# SectionC_BreakOut.net
KiCad netlist of a schematic drawn in Altium Designer
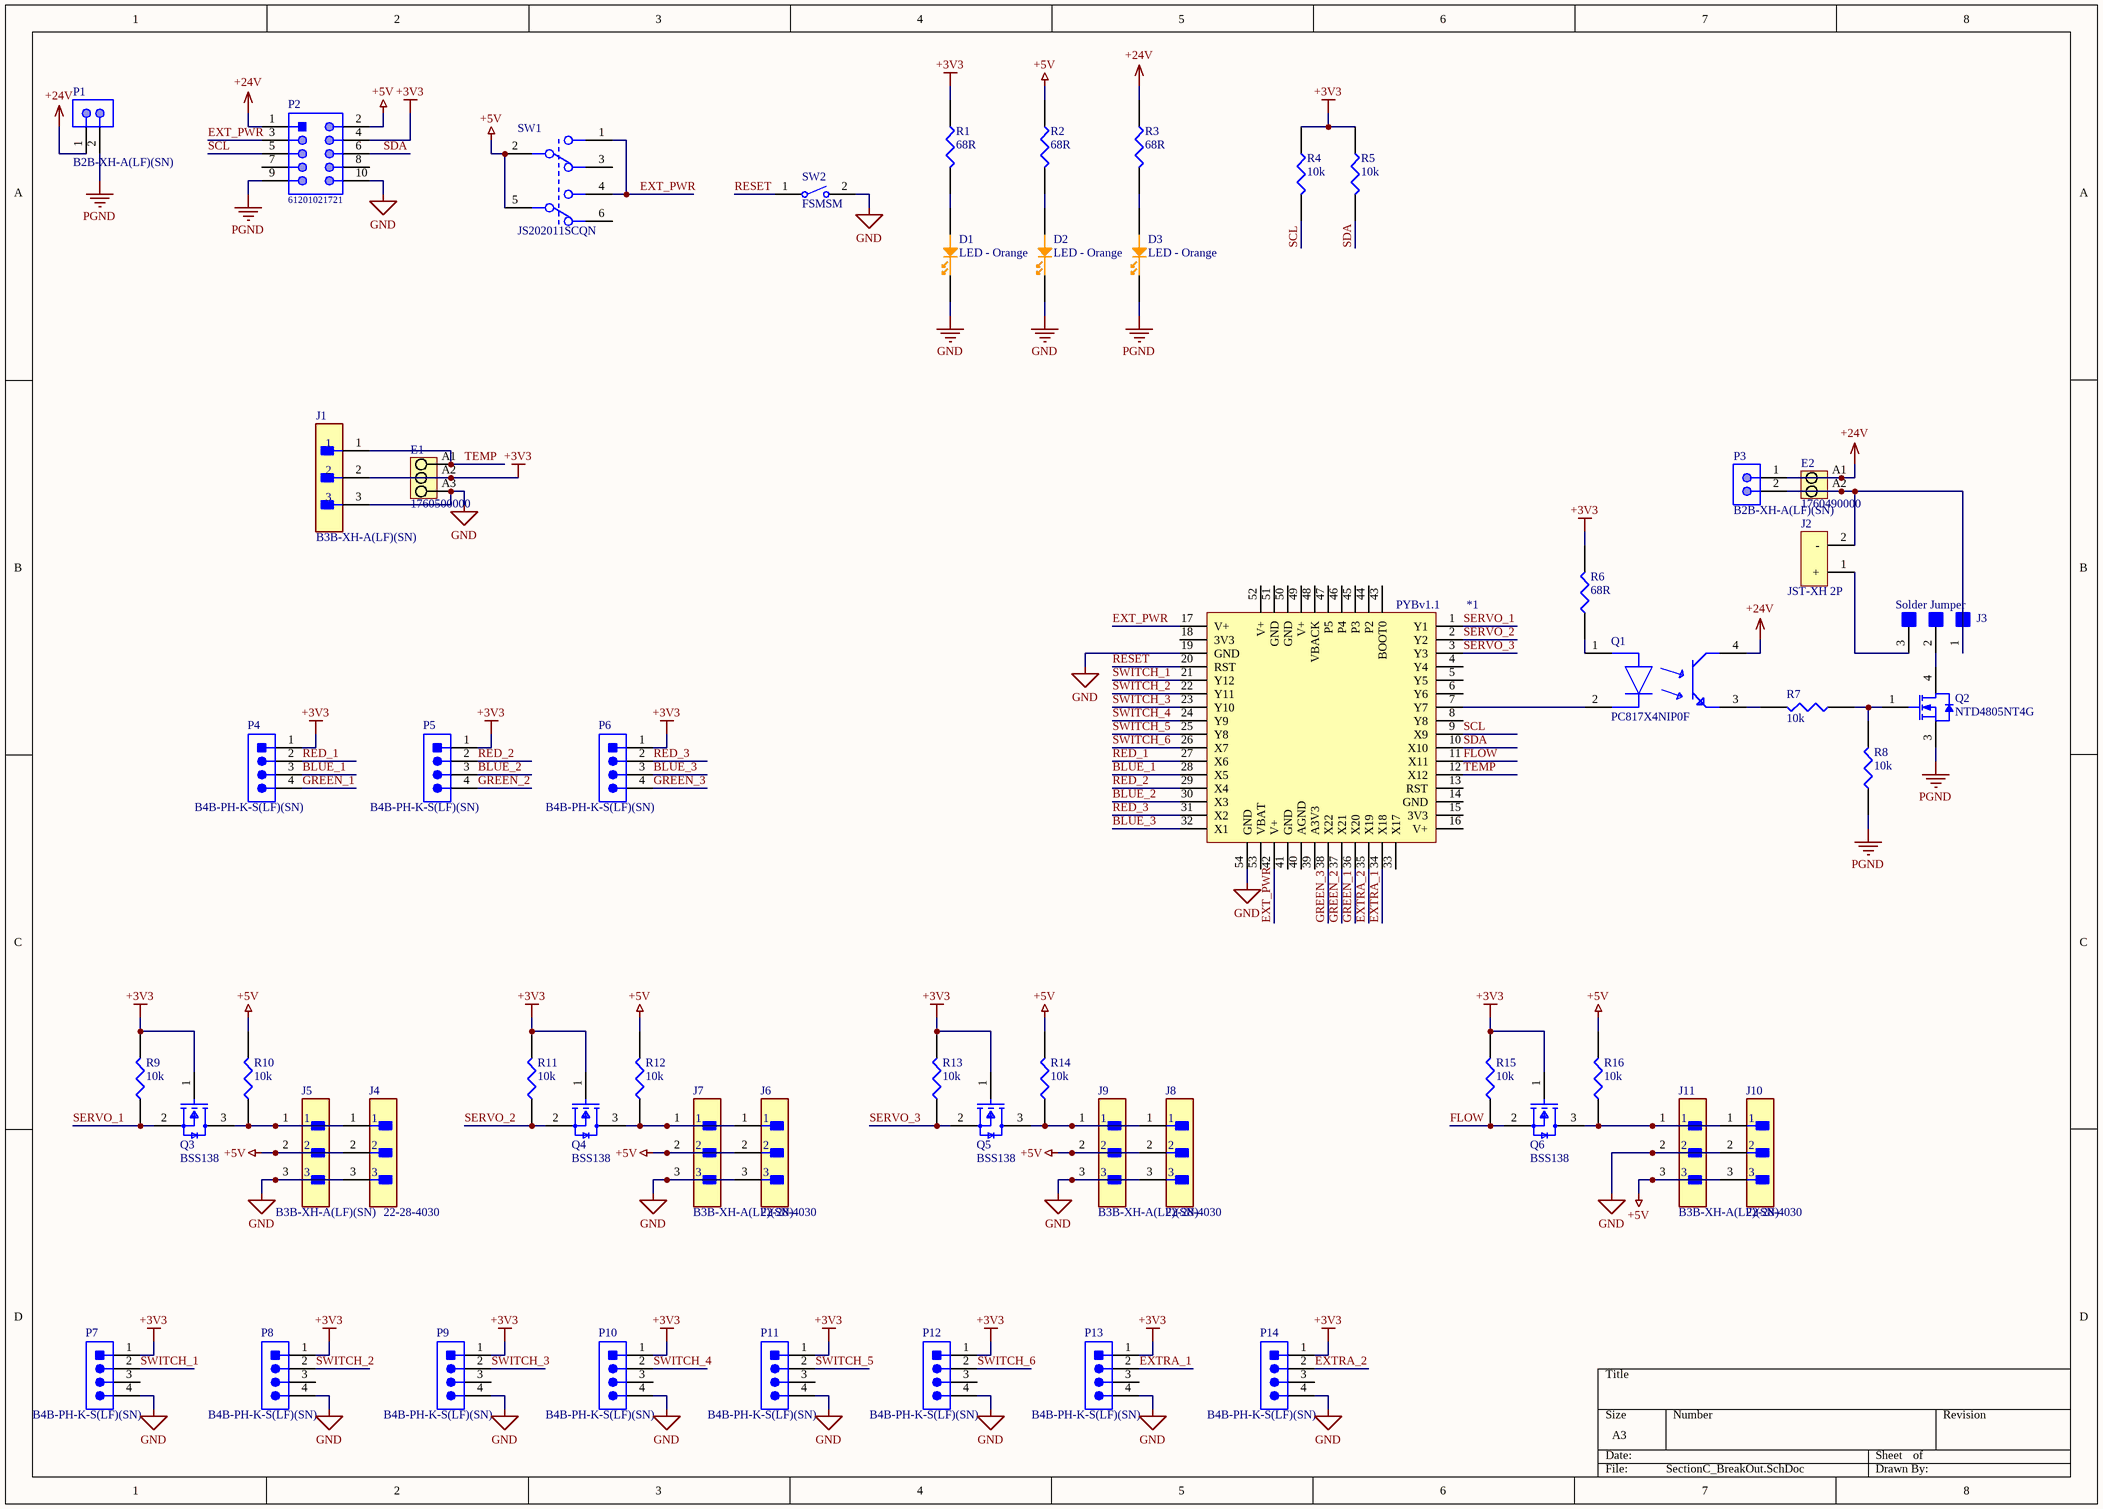
[diagram p0: SectionC_BreakOut.SchDoc]

(export (version "E")
  (design (tool "Eeschema 10.0.6"))
  (components
    (comp (ref "*1")
      (value "PYBv1.1")
      (footprint "PYBv1.1")
      (libsource (lib "SectionC_BreakOut") (part "PYBv1.1"))
    )
    (comp (ref "D1")
      (value "LED - Orange")
      (footprint "LED0603-Orange")
      (description "LED ORANGE CLEAR SMD")
      (fields
        (field (name "MANUFACTURER") "Vishay Lite-On")
        (field (name "MANUFACTURER PART NUMBER") "LTST-C191KFKT")
      )
      (libsource (lib "Limit_Switch_RGB") (part "LTST-C191KFKT"))
    )
    (comp (ref "D2")
      (value "LED - Orange")
      (footprint "LED0603-Orange")
      (description "LED ORANGE CLEAR SMD")
      (fields
        (field (name "MANUFACTURER") "Vishay Lite-On")
        (field (name "MANUFACTURER PART NUMBER") "LTST-C191KFKT")
      )
      (libsource (lib "Limit_Switch_RGB") (part "LTST-C191KFKT"))
    )
    (comp (ref "D3")
      (value "LED - Orange")
      (footprint "LED0603-Orange")
      (description "LED ORANGE CLEAR SMD")
      (fields
        (field (name "MANUFACTURER") "Vishay Lite-On")
        (field (name "MANUFACTURER PART NUMBER") "LTST-C191KFKT")
      )
      (libsource (lib "Limit_Switch_RGB") (part "LTST-C191KFKT"))
    )
    (comp (ref "E1")
      (value "1760500000")
      (footprint "PM_5_08_90_03")
      (description "OMNIMATE Signal - series PM")
      (fields (field (name "MANUFACTURER") "Weidmueller"))
      (libsource (lib "Altium Content Vault") (part "Terminal_03_1x03"))
    )
    (comp (ref "E2")
      (value "1760490000")
      (footprint "PM_5_08_90_02")
      (description "OMNIMATE Signal - series PM")
      (fields (field (name "MANUFACTURER") "Weidmueller"))
      (libsource (lib "Altium Content Vault") (part "Terminal_02_1x02"))
    )
    (comp (ref "J1")
      (value "B3B-XH-A(LF)(SN)")
      (footprint "FP-B3B-XH-A_LF_SN-MFG")
      (description "CONN HEADER VERT 3POS 2.5MM")
      (fields
        (field (name "OCTOPART") "https://octopart.com/b3b-xh-a%28lf%29%28sn%29-jst-3990185")
        (field (name "MANUFACTURER") "JST")
      )
      (libsource (lib "") (part "0d3f023dd272f625e17a2be33dea85f_1"))
    )
    (comp (ref "J2")
      (value "JST-XH 2P")
      (footprint "JST-XH 2P")
      (description "JST-XH 2 POS 2.5mm Solder ST Thru-Hole Box")
      (fields
        (field (name "MANUFACTURER") "JST")
        (field (name "MANUFACTURER PART NUMBER") "B2B-XH-A(LF)(SN)")
      )
      (libsource (lib "SectionE_BreakOut") (part "B2B-XH-A(LF)(SN)"))
    )
    (comp (ref "J3")
      (value "Solder Jumper")
      (footprint "Solder Jumper")
      (libsource (lib "SectionE_BreakOut") (part "Solder Jumper"))
    )
    (comp (ref "J4")
      (value "22-28-4030")
      (footprint "FP-22-28-4030-MFG")
      (description "CONN HEADER VERT 3POS 2.54MM")
      (fields
        (field (name "OCTOPART") "https://octopart.com/0022284030-molex-10476094")
        (field (name "MANUFACTURER") "Molex")
      )
      (libsource (lib "Altium Content Vault") (part "0d3f023dd272f625e17a2be33dea85f"))
    )
    (comp (ref "J5")
      (value "B3B-XH-A(LF)(SN)")
      (footprint "FP-B3B-XH-A_LF_SN-MFG")
      (description "CONN HEADER VERT 3POS 2.5MM")
      (fields
        (field (name "OCTOPART") "https://octopart.com/b3b-xh-a%28lf%29%28sn%29-jst-3990185")
        (field (name "MANUFACTURER") "JST")
      )
      (libsource (lib "Altium Content Vault") (part "0d3f023dd272f625e17a2be33dea85f"))
    )
    (comp (ref "J6")
      (value "22-28-4030")
      (footprint "FP-22-28-4030-MFG")
      (description "CONN HEADER VERT 3POS 2.54MM")
      (fields
        (field (name "OCTOPART") "https://octopart.com/0022284030-molex-10476094")
        (field (name "MANUFACTURER") "Molex")
      )
      (libsource (lib "Altium Content Vault") (part "0d3f023dd272f625e17a2be33dea85f"))
    )
    (comp (ref "J7")
      (value "B3B-XH-A(LF)(SN)")
      (footprint "FP-B3B-XH-A_LF_SN-MFG")
      (description "CONN HEADER VERT 3POS 2.5MM")
      (fields
        (field (name "OCTOPART") "https://octopart.com/b3b-xh-a%28lf%29%28sn%29-jst-3990185")
        (field (name "MANUFACTURER") "JST")
      )
      (libsource (lib "Altium Content Vault") (part "0d3f023dd272f625e17a2be33dea85f"))
    )
    (comp (ref "J8")
      (value "22-28-4030")
      (footprint "FP-22-28-4030-MFG")
      (description "CONN HEADER VERT 3POS 2.54MM")
      (fields
        (field (name "OCTOPART") "https://octopart.com/0022284030-molex-10476094")
        (field (name "MANUFACTURER") "Molex")
      )
      (libsource (lib "Altium Content Vault") (part "0d3f023dd272f625e17a2be33dea85f"))
    )
    (comp (ref "J9")
      (value "B3B-XH-A(LF)(SN)")
      (footprint "FP-B3B-XH-A_LF_SN-MFG")
      (description "CONN HEADER VERT 3POS 2.5MM")
      (fields
        (field (name "OCTOPART") "https://octopart.com/b3b-xh-a%28lf%29%28sn%29-jst-3990185")
        (field (name "MANUFACTURER") "JST")
      )
      (libsource (lib "Altium Content Vault") (part "0d3f023dd272f625e17a2be33dea85f"))
    )
    (comp (ref "J10")
      (value "22-28-4030")
      (footprint "FP-22-28-4030-MFG")
      (description "CONN HEADER VERT 3POS 2.54MM")
      (fields
        (field (name "OCTOPART") "https://octopart.com/0022284030-molex-10476094")
        (field (name "MANUFACTURER") "Molex")
      )
      (libsource (lib "Altium Content Vault") (part "0d3f023dd272f625e17a2be33dea85f"))
    )
    (comp (ref "J11")
      (value "B3B-XH-A(LF)(SN)")
      (footprint "FP-B3B-XH-A_LF_SN-MFG")
      (description "CONN HEADER VERT 3POS 2.5MM")
      (fields
        (field (name "OCTOPART") "https://octopart.com/b3b-xh-a%28lf%29%28sn%29-jst-3990185")
        (field (name "MANUFACTURER") "JST")
      )
      (libsource (lib "Altium Content Vault") (part "0d3f023dd272f625e17a2be33dea85f"))
    )
    (comp (ref "P1")
      (value "B2B-XH-A(LF)(SN)")
      (footprint "JST-B2B-XH-A_V")
      (fields (field (name "MANUFACTURER") "JST"))
      (libsource (lib "") (part "CN-1P-M-R2_1"))
    )
    (comp (ref "P2")
      (value "61201021721")
      (footprint "61201021721")
      (description "Male Box Header WR-BHD, THT, Angled, pitch 2.54 mm, 10 pins")
      (fields (field (name "MANUFACTURER") "Wurth Elektronik") (field (name "PUBLISHER") "WurthElektronik"))
      (libsource (lib "Altium Content Vault") (part "WE-CN-2P-M-R10"))
    )
    (comp (ref "P3")
      (value "B2B-XH-A(LF)(SN)")
      (footprint "JST-B2B-XH-A_V")
      (fields (field (name "MANUFACTURER") "JST"))
      (libsource (lib "Altium Content Vault") (part "CN-1P-M-R2"))
    )
    (comp (ref "P4")
      (value "B4B-PH-K-S(LF)(SN)")
      (footprint "JST-B4B-PH-K-S_V")
      (fields (field (name "MANUFACTURER") "JST"))
      (libsource (lib "Altium Content Vault") (part "CN-1P-M-R4"))
    )
    (comp (ref "P5")
      (value "B4B-PH-K-S(LF)(SN)")
      (footprint "JST-B4B-PH-K-S_V")
      (fields (field (name "MANUFACTURER") "JST"))
      (libsource (lib "Altium Content Vault") (part "CN-1P-M-R4"))
    )
    (comp (ref "P6")
      (value "B4B-PH-K-S(LF)(SN)")
      (footprint "JST-B4B-PH-K-S_V")
      (fields (field (name "MANUFACTURER") "JST"))
      (libsource (lib "Altium Content Vault") (part "CN-1P-M-R4"))
    )
    (comp (ref "P7")
      (value "B4B-PH-K-S(LF)(SN)")
      (footprint "JST-B4B-PH-K-S_V")
      (fields (field (name "MANUFACTURER") "JST"))
      (libsource (lib "Altium Content Vault") (part "CN-1P-M-R4"))
    )
    (comp (ref "P8")
      (value "B4B-PH-K-S(LF)(SN)")
      (footprint "JST-B4B-PH-K-S_V")
      (fields (field (name "MANUFACTURER") "JST"))
      (libsource (lib "Altium Content Vault") (part "CN-1P-M-R4"))
    )
    (comp (ref "P9")
      (value "B4B-PH-K-S(LF)(SN)")
      (footprint "JST-B4B-PH-K-S_V")
      (fields (field (name "MANUFACTURER") "JST"))
      (libsource (lib "Altium Content Vault") (part "CN-1P-M-R4"))
    )
    (comp (ref "P10")
      (value "B4B-PH-K-S(LF)(SN)")
      (footprint "JST-B4B-PH-K-S_V")
      (fields (field (name "MANUFACTURER") "JST"))
      (libsource (lib "Altium Content Vault") (part "CN-1P-M-R4"))
    )
    (comp (ref "P11")
      (value "B4B-PH-K-S(LF)(SN)")
      (footprint "JST-B4B-PH-K-S_V")
      (fields (field (name "MANUFACTURER") "JST"))
      (libsource (lib "Altium Content Vault") (part "CN-1P-M-R4"))
    )
    (comp (ref "P12")
      (value "B4B-PH-K-S(LF)(SN)")
      (footprint "JST-B4B-PH-K-S_V")
      (fields (field (name "MANUFACTURER") "JST"))
      (libsource (lib "Altium Content Vault") (part "CN-1P-M-R4"))
    )
    (comp (ref "P13")
      (value "B4B-PH-K-S(LF)(SN)")
      (footprint "JST-B4B-PH-K-S_V")
      (fields (field (name "MANUFACTURER") "JST"))
      (libsource (lib "Altium Content Vault") (part "CN-1P-M-R4"))
    )
    (comp (ref "P14")
      (value "B4B-PH-K-S(LF)(SN)")
      (footprint "JST-B4B-PH-K-S_V")
      (fields (field (name "MANUFACTURER") "JST"))
      (libsource (lib "Altium Content Vault") (part "CN-1P-M-R4"))
    )
    (comp (ref "Q1")
      (value "PC817X4NIP0F")
      (footprint "FP-PC817X4NIP0F-MFG")
      (description "OPTOISOLATOR 5KV TRANS 4SMD")
      (fields
        (field (name "OCTOPART") "https://octopart.com/pc817x4nip0f-sharp-20650453")
        (field (name "MANUFACTURER") "Sharp")
      )
      (libsource (lib "Altium Content Vault") (part "8ff5844b63c0dea0057760e9ee25456"))
    )
    (comp (ref "Q2")
      (value "NTD4805NT4G")
      (footprint "ONSC-DPAK-3-369AA-01_V")
      (description "Power MOSFET, 30 V, 88 A, Single N-Channel, 3-Pin DPAK, Pb-Free, Tape and Reel")
      (fields (field (name "MANUFACTURER") "On Semiconductor"))
      (libsource (lib "Altium Content Vault") (part "ONSC-NMOS-G1S3D4-3_B"))
    )
    (comp (ref "Q3")
      (value "BSS138")
      (footprint "FP-318-08-IPC_B")
      (description "MOSFET N-CH 50V 220MA SOT-23")
      (libsource (lib "Altium Content Vault") (part "3b9c635fedb024a5347a57b145af9cc"))
    )
    (comp (ref "Q4")
      (value "BSS138")
      (footprint "FP-318-08-IPC_B")
      (description "MOSFET N-CH 50V 220MA SOT-23")
      (libsource (lib "Altium Content Vault") (part "3b9c635fedb024a5347a57b145af9cc"))
    )
    (comp (ref "Q5")
      (value "BSS138")
      (footprint "FP-318-08-IPC_B")
      (description "MOSFET N-CH 50V 220MA SOT-23")
      (libsource (lib "Altium Content Vault") (part "3b9c635fedb024a5347a57b145af9cc"))
    )
    (comp (ref "Q6")
      (value "BSS138")
      (footprint "FP-318-08-IPC_B")
      (description "MOSFET N-CH 50V 220MA SOT-23")
      (libsource (lib "Altium Content Vault") (part "3b9c635fedb024a5347a57b145af9cc"))
    )
    (comp (ref "R1")
      (value "68R")
      (footprint "68R 0603")
      (description "CRGP 0603 68R 1%")
      (fields
        (field (name "MANUFACTURER") "TE Connectivity")
        (field (name "MANUFACTURER PART NUMBER") "CRGP0603F68R")
      )
      (libsource (lib "Limit_Switch_RGB") (part "CRGP0603F68R"))
    )
    (comp (ref "R2")
      (value "68R")
      (footprint "68R 0603")
      (description "CRGP 0603 68R 1%")
      (fields
        (field (name "MANUFACTURER") "TE Connectivity")
        (field (name "MANUFACTURER PART NUMBER") "CRGP0603F68R")
      )
      (libsource (lib "Limit_Switch_RGB") (part "CRGP0603F68R"))
    )
    (comp (ref "R3")
      (value "68R")
      (footprint "68R 0603")
      (description "CRGP 0603 68R 1%")
      (fields
        (field (name "MANUFACTURER") "TE Connectivity")
        (field (name "MANUFACTURER PART NUMBER") "CRGP0603F68R")
      )
      (libsource (lib "Limit_Switch_RGB") (part "CRGP0603F68R"))
    )
    (comp (ref "R4")
      (value "10k")
      (footprint "10k R0603")
      (description "RES 10.0K OHM 1/10W 1% 0603")
      (fields
        (field (name "MANUFACTURER") "TE Connectivity")
        (field (name "MANUFACTURER PART NUMBER") "CRG0603F10K/10")
      )
      (libsource (lib "Limit_Switch_RGB") (part "CRG0603F10K/10"))
    )
    (comp (ref "R5")
      (value "10k")
      (footprint "10k R0603")
      (description "RES 10.0K OHM 1/10W 1% 0603")
      (fields
        (field (name "MANUFACTURER") "TE Connectivity")
        (field (name "MANUFACTURER PART NUMBER") "CRG0603F10K/10")
      )
      (libsource (lib "Limit_Switch_RGB") (part "CRG0603F10K/10"))
    )
    (comp (ref "R6")
      (value "68R")
      (footprint "68R 0603")
      (description "CRGP 0603 68R 1%")
      (fields
        (field (name "MANUFACTURER") "TE Connectivity")
        (field (name "MANUFACTURER PART NUMBER") "CRGP0603F68R")
      )
      (libsource (lib "Limit_Switch_RGB") (part "CRGP0603F68R"))
    )
    (comp (ref "R7")
      (value "10k")
      (footprint "10k R0603")
      (description "RES 10.0K OHM 1/10W 1% 0603")
      (fields
        (field (name "MANUFACTURER") "TE Connectivity")
        (field (name "MANUFACTURER PART NUMBER") "CRG0603F10K/10")
      )
      (libsource (lib "Limit_Switch_RGB") (part "CRG0603F10K/10"))
    )
    (comp (ref "R8")
      (value "10k")
      (footprint "10k R0603")
      (description "RES 10.0K OHM 1/10W 1% 0603")
      (fields
        (field (name "MANUFACTURER") "TE Connectivity")
        (field (name "MANUFACTURER PART NUMBER") "CRG0603F10K/10")
      )
      (libsource (lib "Limit_Switch_RGB") (part "CRG0603F10K/10"))
    )
    (comp (ref "R9")
      (value "10k")
      (footprint "10k R0603")
      (description "RES 10.0K OHM 1/10W 1% 0603")
      (fields
        (field (name "MANUFACTURER") "TE Connectivity")
        (field (name "MANUFACTURER PART NUMBER") "CRG0603F10K/10")
      )
      (libsource (lib "Limit_Switch_RGB") (part "CRG0603F10K/10"))
    )
    (comp (ref "R10")
      (value "10k")
      (footprint "10k R0603")
      (description "RES 10.0K OHM 1/10W 1% 0603")
      (fields
        (field (name "MANUFACTURER") "TE Connectivity")
        (field (name "MANUFACTURER PART NUMBER") "CRG0603F10K/10")
      )
      (libsource (lib "Limit_Switch_RGB") (part "CRG0603F10K/10"))
    )
    (comp (ref "R11")
      (value "10k")
      (footprint "10k R0603")
      (description "RES 10.0K OHM 1/10W 1% 0603")
      (fields
        (field (name "MANUFACTURER") "TE Connectivity")
        (field (name "MANUFACTURER PART NUMBER") "CRG0603F10K/10")
      )
      (libsource (lib "Limit_Switch_RGB") (part "CRG0603F10K/10"))
    )
    (comp (ref "R12")
      (value "10k")
      (footprint "10k R0603")
      (description "RES 10.0K OHM 1/10W 1% 0603")
      (fields
        (field (name "MANUFACTURER") "TE Connectivity")
        (field (name "MANUFACTURER PART NUMBER") "CRG0603F10K/10")
      )
      (libsource (lib "Limit_Switch_RGB") (part "CRG0603F10K/10"))
    )
    (comp (ref "R13")
      (value "10k")
      (footprint "10k R0603")
      (description "RES 10.0K OHM 1/10W 1% 0603")
      (fields
        (field (name "MANUFACTURER") "TE Connectivity")
        (field (name "MANUFACTURER PART NUMBER") "CRG0603F10K/10")
      )
      (libsource (lib "Limit_Switch_RGB") (part "CRG0603F10K/10"))
    )
    (comp (ref "R14")
      (value "10k")
      (footprint "10k R0603")
      (description "RES 10.0K OHM 1/10W 1% 0603")
      (fields
        (field (name "MANUFACTURER") "TE Connectivity")
        (field (name "MANUFACTURER PART NUMBER") "CRG0603F10K/10")
      )
      (libsource (lib "Limit_Switch_RGB") (part "CRG0603F10K/10"))
    )
    (comp (ref "R15")
      (value "10k")
      (footprint "10k R0603")
      (description "RES 10.0K OHM 1/10W 1% 0603")
      (fields
        (field (name "MANUFACTURER") "TE Connectivity")
        (field (name "MANUFACTURER PART NUMBER") "CRG0603F10K/10")
      )
      (libsource (lib "Limit_Switch_RGB") (part "CRG0603F10K/10"))
    )
    (comp (ref "R16")
      (value "10k")
      (footprint "10k R0603")
      (description "RES 10.0K OHM 1/10W 1% 0603")
      (fields
        (field (name "MANUFACTURER") "TE Connectivity")
        (field (name "MANUFACTURER PART NUMBER") "CRG0603F10K/10")
      )
      (libsource (lib "Limit_Switch_RGB") (part "CRG0603F10K/10"))
    )
    (comp (ref "SW1")
      (value "JS202011SCQN")
      (footprint "FP-JS202011SCQN-MFG")
      (description "SWITCH SLIDE DPDT 300MA 6V")
      (libsource (lib "Altium Content Vault") (part "ac99ea1af431c19115f5225061c5c88"))
    )
    (comp (ref "SW2")
      (value "FSMSM")
      (footprint "TECO-FSMSM-2_V")
      (description "FSMSM Push Button Switch, 50 mA, -35 to 85 degC, 2-Pin SMD, RoHS, Bulk")
      (fields (field (name "MANUFACTURER") "TE Connectivity"))
      (libsource (lib "Altium Content Vault") (part "SW-SPST-2_C"))
    )
  )
  (nets
    (net (code "1") (name "+3V3") (class "Default")
      (node (ref "E1") (pin "A2") (pinfunction "A2_A2") (pintype "passive"))
      (node (ref "J1") (pin "2") (pinfunction "2_2") (pintype "passive"))
      (node (ref "P10") (pin "1") (pinfunction "1_1") (pintype "passive"))
      (node (ref "P11") (pin "1") (pinfunction "1_1") (pintype "passive"))
      (node (ref "P12") (pin "1") (pinfunction "1_1") (pintype "passive"))
      (node (ref "P13") (pin "1") (pinfunction "1_1") (pintype "passive"))
      (node (ref "P14") (pin "1") (pinfunction "1_1") (pintype "passive"))
      (node (ref "P2") (pin "4") (pinfunction "4_4") (pintype "passive"))
      (node (ref "P4") (pin "1") (pinfunction "1_1") (pintype "passive"))
      (node (ref "P5") (pin "1") (pinfunction "1_1") (pintype "passive"))
      (node (ref "P6") (pin "1") (pinfunction "1_1") (pintype "passive"))
      (node (ref "P7") (pin "1") (pinfunction "1_1") (pintype "passive"))
      (node (ref "P8") (pin "1") (pinfunction "1_1") (pintype "passive"))
      (node (ref "P9") (pin "1") (pinfunction "1_1") (pintype "passive"))
      (node (ref "Q3") (pin "1") (pinfunction "G_1") (pintype "passive"))
      (node (ref "Q4") (pin "1") (pinfunction "G_1") (pintype "passive"))
      (node (ref "Q5") (pin "1") (pinfunction "G_1") (pintype "passive"))
      (node (ref "Q6") (pin "1") (pinfunction "G_1") (pintype "passive"))
      (node (ref "R1") (pin "1") (pinfunction "1_1") (pintype "passive"))
      (node (ref "R11") (pin "2") (pinfunction "2_2") (pintype "passive"))
      (node (ref "R13") (pin "2") (pinfunction "2_2") (pintype "passive"))
      (node (ref "R15") (pin "2") (pinfunction "2_2") (pintype "passive"))
      (node (ref "R4") (pin "1") (pinfunction "1_1") (pintype "passive"))
      (node (ref "R5") (pin "1") (pinfunction "1_1") (pintype "passive"))
      (node (ref "R6") (pin "2") (pinfunction "2_2") (pintype "passive"))
      (node (ref "R9") (pin "2") (pinfunction "2_2") (pintype "passive"))
    )
    (net (code "2") (name "+5V") (class "Default")
      (node (ref "J10") (pin "3") (pinfunction "3_3") (pintype "passive"))
      (node (ref "J11") (pin "3") (pinfunction "3_3") (pintype "passive"))
      (node (ref "J4") (pin "2") (pinfunction "2_2") (pintype "passive"))
      (node (ref "J5") (pin "2") (pinfunction "2_2") (pintype "passive"))
      (node (ref "J6") (pin "2") (pinfunction "2_2") (pintype "passive"))
      (node (ref "J7") (pin "2") (pinfunction "2_2") (pintype "passive"))
      (node (ref "J8") (pin "2") (pinfunction "2_2") (pintype "passive"))
      (node (ref "J9") (pin "2") (pinfunction "2_2") (pintype "passive"))
      (node (ref "P2") (pin "2") (pinfunction "2_2") (pintype "passive"))
      (node (ref "R10") (pin "2") (pinfunction "2_2") (pintype "passive"))
      (node (ref "R12") (pin "2") (pinfunction "2_2") (pintype "passive"))
      (node (ref "R14") (pin "2") (pinfunction "2_2") (pintype "passive"))
      (node (ref "R16") (pin "2") (pinfunction "2_2") (pintype "passive"))
      (node (ref "R2") (pin "1") (pinfunction "1_1") (pintype "passive"))
      (node (ref "SW1") (pin "2") (pinfunction "2_2") (pintype "passive"))
      (node (ref "SW1") (pin "5") (pinfunction "5_5") (pintype "passive"))
    )
    (net (code "3") (name "+24V") (class "Default")
      (node (ref "E2") (pin "A1") (pinfunction "A1_A1") (pintype "passive"))
      (node (ref "P1") (pin "1") (pinfunction "1_1") (pintype "passive"))
      (node (ref "P2") (pin "1") (pinfunction "1_1") (pintype "passive"))
      (node (ref "P3") (pin "1") (pinfunction "1_1") (pintype "passive"))
      (node (ref "Q1") (pin "4") (pinfunction "C_4") (pintype "passive"))
      (node (ref "R3") (pin "1") (pinfunction "1_1") (pintype "passive"))
    )
    (net (code "4") (name "/BLUE_1") (class "Default")
      (node (ref "*1") (pin "28") (pinfunction "X5_28") (pintype "passive"))
      (node (ref "P4") (pin "3") (pinfunction "3_3") (pintype "passive"))
    )
    (net (code "5") (name "/BLUE_2") (class "Default")
      (node (ref "*1") (pin "30") (pinfunction "X3_30") (pintype "passive"))
      (node (ref "P5") (pin "3") (pinfunction "3_3") (pintype "passive"))
    )
    (net (code "6") (name "/BLUE_3") (class "Default")
      (node (ref "*1") (pin "32") (pinfunction "X1_32") (pintype "passive"))
      (node (ref "P6") (pin "3") (pinfunction "3_3") (pintype "passive"))
    )
    (net (code "7") (name "/EXTRA_1") (class "Default")
      (node (ref "*1") (pin "34") (pinfunction "X18_34") (pintype "passive"))
      (node (ref "P13") (pin "2") (pinfunction "2_2") (pintype "passive"))
    )
    (net (code "8") (name "/EXTRA_2") (class "Default")
      (node (ref "*1") (pin "35") (pinfunction "X19_35") (pintype "passive"))
      (node (ref "P14") (pin "2") (pinfunction "2_2") (pintype "passive"))
    )
    (net (code "9") (name "/EXT_PWR") (class "Default")
      (node (ref "*1") (pin "17") (pinfunction "V+_17") (pintype "passive"))
      (node (ref "*1") (pin "42") (pinfunction "V+_42") (pintype "passive"))
      (node (ref "P2") (pin "3") (pinfunction "3_3") (pintype "passive"))
      (node (ref "SW1") (pin "1") (pinfunction "1_1") (pintype "passive"))
      (node (ref "SW1") (pin "4") (pinfunction "4_4") (pintype "passive"))
    )
    (net (code "10") (name "/FLOW") (class "Default")
      (node (ref "*1") (pin "11") (pinfunction "X11_11") (pintype "passive"))
      (node (ref "Q6") (pin "2") (pinfunction "S_2") (pintype "passive"))
      (node (ref "R15") (pin "1") (pinfunction "1_1") (pintype "passive"))
    )
    (net (code "11") (name "/GREEN_1") (class "Default")
      (node (ref "*1") (pin "36") (pinfunction "X20_36") (pintype "passive"))
      (node (ref "P4") (pin "4") (pinfunction "4_4") (pintype "passive"))
    )
    (net (code "12") (name "/GREEN_2") (class "Default")
      (node (ref "*1") (pin "37") (pinfunction "X21_37") (pintype "passive"))
      (node (ref "P5") (pin "4") (pinfunction "4_4") (pintype "passive"))
    )
    (net (code "13") (name "/GREEN_3") (class "Default")
      (node (ref "*1") (pin "38") (pinfunction "X22_38") (pintype "passive"))
      (node (ref "P6") (pin "4") (pinfunction "4_4") (pintype "passive"))
    )
    (net (code "14") (name "/RED_1") (class "Default")
      (node (ref "*1") (pin "27") (pinfunction "X6_27") (pintype "passive"))
      (node (ref "P4") (pin "2") (pinfunction "2_2") (pintype "passive"))
    )
    (net (code "15") (name "/RED_2") (class "Default")
      (node (ref "*1") (pin "29") (pinfunction "X4_29") (pintype "passive"))
      (node (ref "P5") (pin "2") (pinfunction "2_2") (pintype "passive"))
    )
    (net (code "16") (name "/RED_3") (class "Default")
      (node (ref "*1") (pin "31") (pinfunction "X2_31") (pintype "passive"))
      (node (ref "P6") (pin "2") (pinfunction "2_2") (pintype "passive"))
    )
    (net (code "17") (name "/RESET") (class "Default")
      (node (ref "*1") (pin "20") (pinfunction "RST_20") (pintype "passive"))
      (node (ref "SW2") (pin "1") (pinfunction "1_1") (pintype "passive"))
    )
    (net (code "18") (name "/SCL") (class "Default")
      (node (ref "*1") (pin "9") (pinfunction "X9_9") (pintype "passive"))
      (node (ref "P2") (pin "5") (pinfunction "5_5") (pintype "passive"))
      (node (ref "R4") (pin "2") (pinfunction "2_2") (pintype "passive"))
    )
    (net (code "19") (name "/SDA") (class "Default")
      (node (ref "*1") (pin "10") (pinfunction "X10_10") (pintype "passive"))
      (node (ref "P2") (pin "6") (pinfunction "6_6") (pintype "passive"))
      (node (ref "R5") (pin "2") (pinfunction "2_2") (pintype "passive"))
    )
    (net (code "20") (name "/SERVO_1") (class "Default")
      (node (ref "*1") (pin "1") (pinfunction "Y1_1") (pintype "passive"))
      (node (ref "Q3") (pin "2") (pinfunction "S_2") (pintype "passive"))
      (node (ref "R9") (pin "1") (pinfunction "1_1") (pintype "passive"))
    )
    (net (code "21") (name "/SERVO_2") (class "Default")
      (node (ref "*1") (pin "2") (pinfunction "Y2_2") (pintype "passive"))
      (node (ref "Q4") (pin "2") (pinfunction "S_2") (pintype "passive"))
      (node (ref "R11") (pin "1") (pinfunction "1_1") (pintype "passive"))
    )
    (net (code "22") (name "/SERVO_3") (class "Default")
      (node (ref "*1") (pin "3") (pinfunction "Y3_3") (pintype "passive"))
      (node (ref "Q5") (pin "2") (pinfunction "S_2") (pintype "passive"))
      (node (ref "R13") (pin "1") (pinfunction "1_1") (pintype "passive"))
    )
    (net (code "23") (name "/SWITCH_1") (class "Default")
      (node (ref "*1") (pin "21") (pinfunction "Y12_21") (pintype "passive"))
      (node (ref "P7") (pin "2") (pinfunction "2_2") (pintype "passive"))
    )
    (net (code "24") (name "/SWITCH_2") (class "Default")
      (node (ref "*1") (pin "22") (pinfunction "Y11_22") (pintype "passive"))
      (node (ref "P8") (pin "2") (pinfunction "2_2") (pintype "passive"))
    )
    (net (code "25") (name "/SWITCH_3") (class "Default")
      (node (ref "*1") (pin "23") (pinfunction "Y10_23") (pintype "passive"))
      (node (ref "P9") (pin "2") (pinfunction "2_2") (pintype "passive"))
    )
    (net (code "26") (name "/SWITCH_4") (class "Default")
      (node (ref "*1") (pin "24") (pinfunction "Y9_24") (pintype "passive"))
      (node (ref "P10") (pin "2") (pinfunction "2_2") (pintype "passive"))
    )
    (net (code "27") (name "/SWITCH_5") (class "Default")
      (node (ref "*1") (pin "25") (pinfunction "Y8_25") (pintype "passive"))
      (node (ref "P11") (pin "2") (pinfunction "2_2") (pintype "passive"))
    )
    (net (code "28") (name "/SWITCH_6") (class "Default")
      (node (ref "*1") (pin "26") (pinfunction "X7_26") (pintype "passive"))
      (node (ref "P12") (pin "2") (pinfunction "2_2") (pintype "passive"))
    )
    (net (code "29") (name "/TEMP") (class "Default")
      (node (ref "*1") (pin "12") (pinfunction "X12_12") (pintype "passive"))
      (node (ref "E1") (pin "A1") (pinfunction "A1_A1") (pintype "passive"))
      (node (ref "J1") (pin "1") (pinfunction "1_1") (pintype "passive"))
    )
    (net (code "30") (name "GND") (class "Default")
      (node (ref "*1") (pin "19") (pinfunction "GND_19") (pintype "passive"))
      (node (ref "*1") (pin "54") (pinfunction "GND_54") (pintype "passive"))
      (node (ref "D1") (pin "1") (pinfunction "Cathode_1") (pintype "passive"))
      (node (ref "D2") (pin "1") (pinfunction "Cathode_1") (pintype "passive"))
      (node (ref "E1") (pin "A3") (pinfunction "A3_A3") (pintype "passive"))
      (node (ref "J1") (pin "3") (pinfunction "3_3") (pintype "passive"))
      (node (ref "J10") (pin "2") (pinfunction "2_2") (pintype "passive"))
      (node (ref "J11") (pin "2") (pinfunction "2_2") (pintype "passive"))
      (node (ref "J4") (pin "3") (pinfunction "3_3") (pintype "passive"))
      (node (ref "J5") (pin "3") (pinfunction "3_3") (pintype "passive"))
      (node (ref "J6") (pin "3") (pinfunction "3_3") (pintype "passive"))
      (node (ref "J7") (pin "3") (pinfunction "3_3") (pintype "passive"))
      (node (ref "J8") (pin "3") (pinfunction "3_3") (pintype "passive"))
      (node (ref "J9") (pin "3") (pinfunction "3_3") (pintype "passive"))
      (node (ref "P10") (pin "4") (pinfunction "4_4") (pintype "passive"))
      (node (ref "P11") (pin "4") (pinfunction "4_4") (pintype "passive"))
      (node (ref "P12") (pin "4") (pinfunction "4_4") (pintype "passive"))
      (node (ref "P13") (pin "4") (pinfunction "4_4") (pintype "passive"))
      (node (ref "P14") (pin "4") (pinfunction "4_4") (pintype "passive"))
      (node (ref "P2") (pin "10") (pinfunction "10_10") (pintype "passive"))
      (node (ref "P7") (pin "4") (pinfunction "4_4") (pintype "passive"))
      (node (ref "P8") (pin "4") (pinfunction "4_4") (pintype "passive"))
      (node (ref "P9") (pin "4") (pinfunction "4_4") (pintype "passive"))
      (node (ref "SW2") (pin "2") (pinfunction "2_2") (pintype "passive"))
    )
    (net (code "31") (name "Net-(*1-Y7)") (class "Default")
      (node (ref "*1") (pin "7") (pinfunction "Y7_7") (pintype "passive"))
      (node (ref "Q1") (pin "2") (pinfunction "C_2") (pintype "passive"))
    )
    (net (code "32") (name "Net-(D1-Anode)") (class "Default")
      (node (ref "D1") (pin "2") (pinfunction "Anode_2") (pintype "passive"))
      (node (ref "R1") (pin "2") (pinfunction "2_2") (pintype "passive"))
    )
    (net (code "33") (name "Net-(D2-Anode)") (class "Default")
      (node (ref "D2") (pin "2") (pinfunction "Anode_2") (pintype "passive"))
      (node (ref "R2") (pin "2") (pinfunction "2_2") (pintype "passive"))
    )
    (net (code "34") (name "Net-(D3-Anode)") (class "Default")
      (node (ref "D3") (pin "2") (pinfunction "Anode_2") (pintype "passive"))
      (node (ref "R3") (pin "2") (pinfunction "2_2") (pintype "passive"))
    )
    (net (code "35") (name "Net-(J2-+)") (class "Default")
      (node (ref "J2") (pin "1") (pinfunction "+_1") (pintype "passive"))
      (node (ref "J3") (pin "3") (pinfunction "3_3") (pintype "passive"))
    )
    (net (code "36") (name "Net-(J2--)") (class "Default")
      (node (ref "E2") (pin "A2") (pinfunction "A2_A2") (pintype "passive"))
      (node (ref "J2") (pin "2") (pinfunction "-_2") (pintype "passive"))
      (node (ref "J3") (pin "1") (pinfunction "1_1") (pintype "passive"))
      (node (ref "P3") (pin "2") (pinfunction "2_2") (pintype "passive"))
    )
    (net (code "37") (name "Net-(Q1-A)") (class "Default")
      (node (ref "Q1") (pin "1") (pinfunction "A_1") (pintype "passive"))
      (node (ref "R6") (pin "1") (pinfunction "1_1") (pintype "passive"))
    )
    (net (code "38") (name "Net-(Q1-E)") (class "Default")
      (node (ref "Q1") (pin "3") (pinfunction "E_3") (pintype "passive"))
      (node (ref "R7") (pin "2") (pinfunction "2_2") (pintype "passive"))
    )
    (net (code "39") (name "Net-(Q2-D)") (class "Default")
      (node (ref "J3") (pin "2") (pinfunction "2_2") (pintype "passive"))
      (node (ref "Q2") (pin "4") (pinfunction "D_4") (pintype "passive"))
    )
    (net (code "40") (name "Net-(Q2-G)") (class "Default")
      (node (ref "Q2") (pin "1") (pinfunction "G_1") (pintype "passive"))
      (node (ref "R7") (pin "1") (pinfunction "1_1") (pintype "passive"))
      (node (ref "R8") (pin "2") (pinfunction "2_2") (pintype "passive"))
    )
    (net (code "41") (name "Net-(Q3-D)") (class "Default")
      (node (ref "J4") (pin "1") (pinfunction "1_1") (pintype "passive"))
      (node (ref "J5") (pin "1") (pinfunction "1_1") (pintype "passive"))
      (node (ref "Q3") (pin "3") (pinfunction "D_3") (pintype "passive"))
      (node (ref "R10") (pin "1") (pinfunction "1_1") (pintype "passive"))
    )
    (net (code "42") (name "Net-(Q4-D)") (class "Default")
      (node (ref "J6") (pin "1") (pinfunction "1_1") (pintype "passive"))
      (node (ref "J7") (pin "1") (pinfunction "1_1") (pintype "passive"))
      (node (ref "Q4") (pin "3") (pinfunction "D_3") (pintype "passive"))
      (node (ref "R12") (pin "1") (pinfunction "1_1") (pintype "passive"))
    )
    (net (code "43") (name "Net-(Q5-D)") (class "Default")
      (node (ref "J8") (pin "1") (pinfunction "1_1") (pintype "passive"))
      (node (ref "J9") (pin "1") (pinfunction "1_1") (pintype "passive"))
      (node (ref "Q5") (pin "3") (pinfunction "D_3") (pintype "passive"))
      (node (ref "R14") (pin "1") (pinfunction "1_1") (pintype "passive"))
    )
    (net (code "44") (name "Net-(Q6-D)") (class "Default")
      (node (ref "J10") (pin "1") (pinfunction "1_1") (pintype "passive"))
      (node (ref "J11") (pin "1") (pinfunction "1_1") (pintype "passive"))
      (node (ref "Q6") (pin "3") (pinfunction "D_3") (pintype "passive"))
      (node (ref "R16") (pin "1") (pinfunction "1_1") (pintype "passive"))
    )
    (net (code "45") (name "PGND") (class "Default")
      (node (ref "D3") (pin "1") (pinfunction "Cathode_1") (pintype "passive"))
      (node (ref "P1") (pin "2") (pinfunction "2_2") (pintype "passive"))
      (node (ref "P2") (pin "9") (pinfunction "9_9") (pintype "passive"))
      (node (ref "Q2") (pin "3") (pinfunction "S_3") (pintype "passive"))
      (node (ref "R8") (pin "1") (pinfunction "1_1") (pintype "passive"))
    )
    (net (code "46") (name "unconnected-(*1-3V3-Pad15)") (class "Default")
      (node (ref "*1") (pin "15") (pinfunction "3V3_15") (pintype "passive"))
    )
    (net (code "47") (name "unconnected-(*1-3V3-Pad18)") (class "Default")
      (node (ref "*1") (pin "18") (pinfunction "3V3_18") (pintype "passive"))
    )
    (net (code "48") (name "unconnected-(*1-A3V3-Pad39)") (class "Default")
      (node (ref "*1") (pin "39") (pinfunction "A3V3_39") (pintype "passive"))
    )
    (net (code "49") (name "unconnected-(*1-AGND-Pad40)") (class "Default")
      (node (ref "*1") (pin "40") (pinfunction "AGND_40") (pintype "passive"))
    )
    (net (code "50") (name "unconnected-(*1-BOOT0-Pad43)") (class "Default")
      (node (ref "*1") (pin "43") (pinfunction "BOOT0_43") (pintype "passive"))
    )
    (net (code "51") (name "unconnected-(*1-GND-Pad14)") (class "Default")
      (node (ref "*1") (pin "14") (pinfunction "GND_14") (pintype "passive"))
    )
    (net (code "52") (name "unconnected-(*1-GND-Pad41)") (class "Default")
      (node (ref "*1") (pin "41") (pinfunction "GND_41") (pintype "passive"))
    )
    (net (code "53") (name "unconnected-(*1-GND-Pad50)") (class "Default")
      (node (ref "*1") (pin "50") (pinfunction "GND_50") (pintype "passive"))
    )
    (net (code "54") (name "unconnected-(*1-GND-Pad51)") (class "Default")
      (node (ref "*1") (pin "51") (pinfunction "GND_51") (pintype "passive"))
    )
    (net (code "55") (name "unconnected-(*1-P2-Pad44)") (class "Default")
      (node (ref "*1") (pin "44") (pinfunction "P2_44") (pintype "passive"))
    )
    (net (code "56") (name "unconnected-(*1-P3-Pad45)") (class "Default")
      (node (ref "*1") (pin "45") (pinfunction "P3_45") (pintype "passive"))
    )
    (net (code "57") (name "unconnected-(*1-P4-Pad46)") (class "Default")
      (node (ref "*1") (pin "46") (pinfunction "P4_46") (pintype "passive"))
    )
    (net (code "58") (name "unconnected-(*1-P5-Pad47)") (class "Default")
      (node (ref "*1") (pin "47") (pinfunction "P5_47") (pintype "passive"))
    )
    (net (code "59") (name "unconnected-(*1-RST-Pad13)") (class "Default")
      (node (ref "*1") (pin "13") (pinfunction "RST_13") (pintype "passive"))
    )
    (net (code "60") (name "unconnected-(*1-V+-Pad16)") (class "Default")
      (node (ref "*1") (pin "16") (pinfunction "V+_16") (pintype "passive"))
    )
    (net (code "61") (name "unconnected-(*1-V+-Pad49)") (class "Default")
      (node (ref "*1") (pin "49") (pinfunction "V+_49") (pintype "passive"))
    )
    (net (code "62") (name "unconnected-(*1-V+-Pad52)") (class "Default")
      (node (ref "*1") (pin "52") (pinfunction "V+_52") (pintype "passive"))
    )
    (net (code "63") (name "unconnected-(*1-VBACK-Pad48)") (class "Default")
      (node (ref "*1") (pin "48") (pinfunction "VBACK_48") (pintype "passive"))
    )
    (net (code "64") (name "unconnected-(*1-VBAT-Pad53)") (class "Default")
      (node (ref "*1") (pin "53") (pinfunction "VBAT_53") (pintype "passive"))
    )
    (net (code "65") (name "unconnected-(*1-X17-Pad33)") (class "Default")
      (node (ref "*1") (pin "33") (pinfunction "X17_33") (pintype "passive"))
    )
    (net (code "66") (name "unconnected-(*1-Y4-Pad4)") (class "Default")
      (node (ref "*1") (pin "4") (pinfunction "Y4_4") (pintype "passive"))
    )
    (net (code "67") (name "unconnected-(*1-Y5-Pad5)") (class "Default")
      (node (ref "*1") (pin "5") (pinfunction "Y5_5") (pintype "passive"))
    )
    (net (code "68") (name "unconnected-(*1-Y6-Pad6)") (class "Default")
      (node (ref "*1") (pin "6") (pinfunction "Y6_6") (pintype "passive"))
    )
    (net (code "69") (name "unconnected-(*1-Y8-Pad8)") (class "Default")
      (node (ref "*1") (pin "8") (pinfunction "Y8_8") (pintype "passive"))
    )
    (net (code "70") (name "unconnected-(P2-Pad7)") (class "Default")
      (node (ref "P2") (pin "7") (pinfunction "7_7") (pintype "passive"))
    )
    (net (code "71") (name "unconnected-(P2-Pad8)") (class "Default")
      (node (ref "P2") (pin "8") (pinfunction "8_8") (pintype "passive"))
    )
    (net (code "72") (name "unconnected-(P7-Pad3)") (class "Default")
      (node (ref "P7") (pin "3") (pinfunction "3_3") (pintype "passive"))
    )
    (net (code "73") (name "unconnected-(P8-Pad3)") (class "Default")
      (node (ref "P8") (pin "3") (pinfunction "3_3") (pintype "passive"))
    )
    (net (code "74") (name "unconnected-(P9-Pad3)") (class "Default")
      (node (ref "P9") (pin "3") (pinfunction "3_3") (pintype "passive"))
    )
    (net (code "75") (name "unconnected-(P10-Pad3)") (class "Default")
      (node (ref "P10") (pin "3") (pinfunction "3_3") (pintype "passive"))
    )
    (net (code "76") (name "unconnected-(P11-Pad3)") (class "Default")
      (node (ref "P11") (pin "3") (pinfunction "3_3") (pintype "passive"))
    )
    (net (code "77") (name "unconnected-(P12-Pad3)") (class "Default")
      (node (ref "P12") (pin "3") (pinfunction "3_3") (pintype "passive"))
    )
    (net (code "78") (name "unconnected-(P13-Pad3)") (class "Default")
      (node (ref "P13") (pin "3") (pinfunction "3_3") (pintype "passive"))
    )
    (net (code "79") (name "unconnected-(P14-Pad3)") (class "Default")
      (node (ref "P14") (pin "3") (pinfunction "3_3") (pintype "passive"))
    )
    (net (code "80") (name "unconnected-(SW1-Pad3)") (class "Default")
      (node (ref "SW1") (pin "3") (pinfunction "3_3") (pintype "passive"))
    )
    (net (code "81") (name "unconnected-(SW1-Pad6)") (class "Default")
      (node (ref "SW1") (pin "6") (pinfunction "6_6") (pintype "passive"))
    )
  )
)
